# ecg.net
KiCad netlist of a schematic drawn in Altium Designer
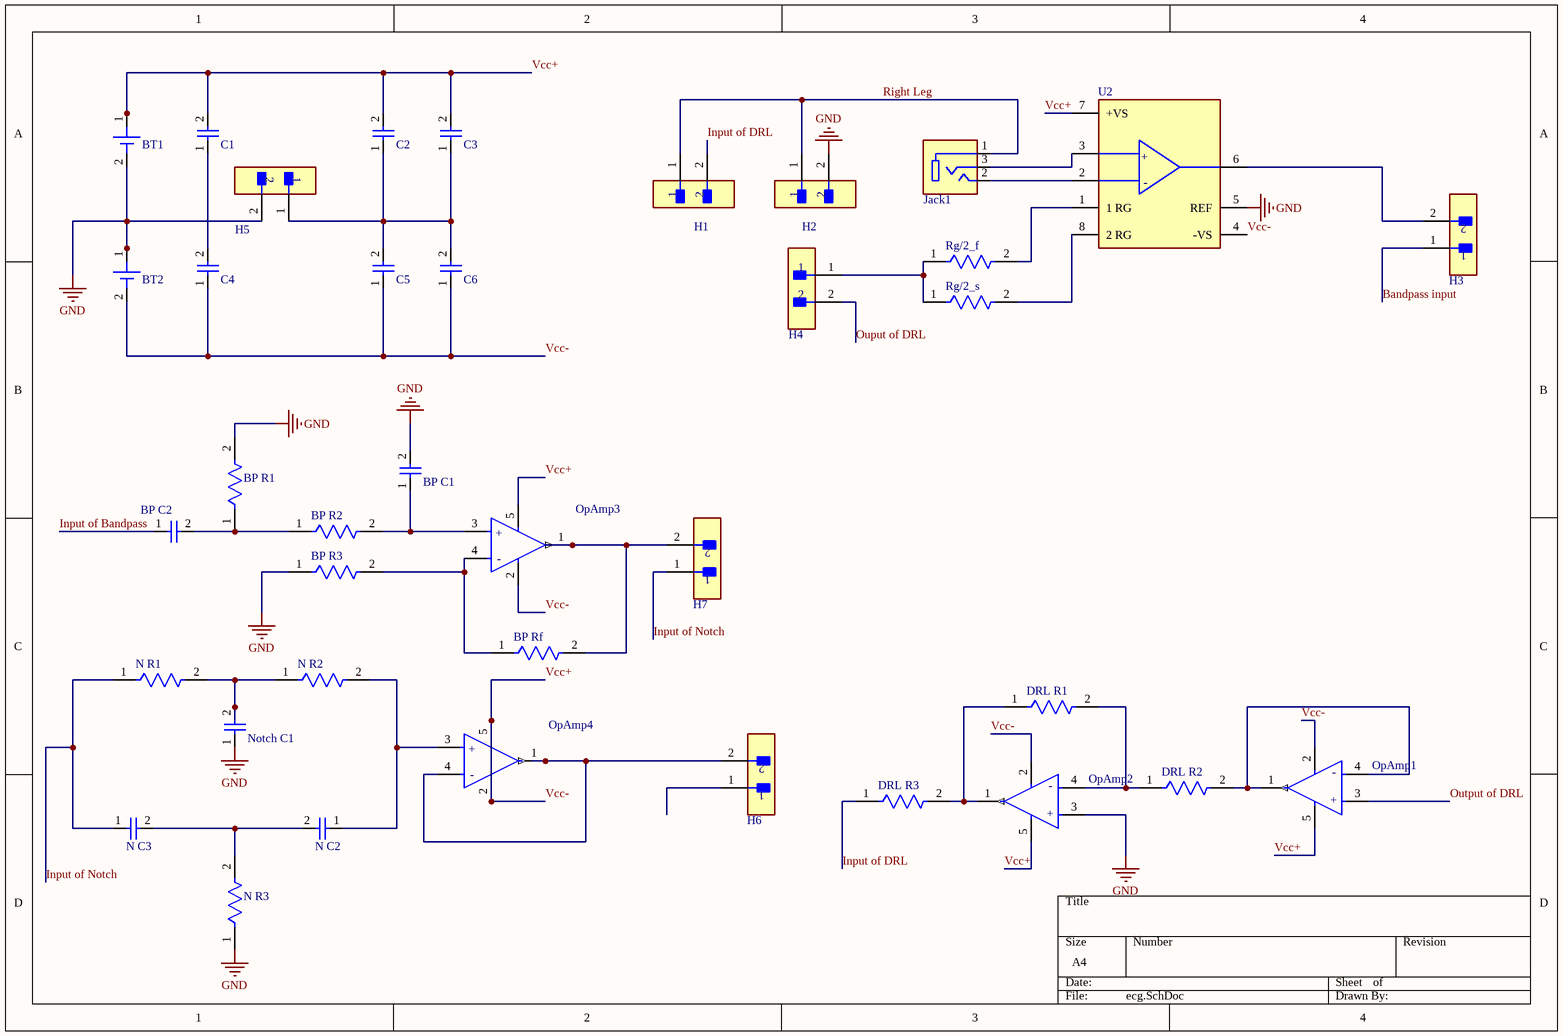
[diagram p0: ecg.SchDoc]

(export (version "E")
  (design (tool "Eeschema 10.0.6"))
  (components
    (comp (ref "BP C1")
      (value "08052U220GAT2A")
      (footprint "CAPC2013X115X51ML20T26")
      (fields (field (name "MANUFACTURER") "AVX Interconnect / Elco"))
      (libsource (lib "Sushil_PCB") (part "CMP-2007-04866-1"))
    )
    (comp (ref "BP C2")
      (value "08052U220GAT2A")
      (footprint "CAPC2013X115X51ML20T26")
      (fields (field (name "MANUFACTURER") "AVX Interconnect / Elco"))
      (libsource (lib "Sushil_PCB") (part "CMP-2007-04866-1"))
    )
    (comp (ref "BP R1")
      (value "CRCW08053K30FKEA")
      (footprint "FP-CRCW0805-e3-MFG")
      (description "RES Thick Film, 3.3kΩ, 1%, 0.125W, 100ppm/°C, 0805")
      (fields (field (name "TOLERANCE") "1%"))
      (libsource (lib "Sushil_PCB") (part "CMP-2001-03876-2"))
    )
    (comp (ref "BP R2")
      (value "CRCW08053K30FKEA")
      (footprint "FP-CRCW0805-e3-MFG")
      (description "RES Thick Film, 3.3kΩ, 1%, 0.125W, 100ppm/°C, 0805")
      (fields (field (name "TOLERANCE") "1%"))
      (libsource (lib "Sushil_PCB") (part "CMP-2001-03876-2"))
    )
    (comp (ref "BP R3")
      (value "CRCW08053K30FKEA")
      (footprint "FP-CRCW0805-e3-MFG")
      (description "RES Thick Film, 3.3kΩ, 1%, 0.125W, 100ppm/°C, 0805")
      (fields (field (name "TOLERANCE") "1%"))
      (libsource (lib "Sushil_PCB") (part "CMP-2001-03876-2"))
    )
    (comp (ref "BP Rf")
      (value "CRCW08053K30FKEA")
      (footprint "FP-CRCW0805-e3-MFG")
      (description "RES Thick Film, 3.3kΩ, 1%, 0.125W, 100ppm/°C, 0805")
      (fields (field (name "TOLERANCE") "1%"))
      (libsource (lib "Sushil_PCB") (part "CMP-2001-03876-2"))
    )
    (comp (ref "BT1")
      (value "BK-913-TR")
      (footprint "BAT_BK-913-TR")
      (description "Battery Retainer Coin, 20.0mm 1 Cell PC Pin")
      (fields (field (name "DIGI-KEY_PART_NUMBER") "BK-913-CT-ND") (field (name "MF") "MPD (Memory"))
      (libsource (lib "Sushil_PCB") (part "BK-913-TR"))
    )
    (comp (ref "BT2")
      (value "BK-913-TR")
      (footprint "BAT_BK-913-TR")
      (description "Battery Retainer Coin, 20.0mm 1 Cell PC Pin")
      (fields (field (name "DIGI-KEY_PART_NUMBER") "BK-913-CT-ND") (field (name "MF") "MPD (Memory"))
      (libsource (lib "Sushil_PCB") (part "BK-913-TR"))
    )
    (comp (ref "C1")
      (value "08052U220GAT2A")
      (footprint "CAPC2013X115X51ML20T26")
      (fields (field (name "MANUFACTURER") "AVX Interconnect / Elco"))
      (libsource (lib "Sushil_PCB") (part "CMP-2007-04866-1"))
    )
    (comp (ref "C2")
      (value "08052U220GAT2A")
      (footprint "CAPC2013X115X51ML20T26")
      (fields (field (name "MANUFACTURER") "AVX Interconnect / Elco"))
      (libsource (lib "Sushil_PCB") (part "CMP-2007-04866-1"))
    )
    (comp (ref "C3")
      (value "08052U220GAT2A")
      (footprint "CAPC2013X115X51ML20T26")
      (fields (field (name "MANUFACTURER") "AVX Interconnect / Elco"))
      (libsource (lib "Sushil_PCB") (part "CMP-2007-04866-1"))
    )
    (comp (ref "C4")
      (value "08052U220GAT2A")
      (footprint "CAPC2013X115X51ML20T26")
      (fields (field (name "MANUFACTURER") "AVX Interconnect / Elco"))
      (libsource (lib "Sushil_PCB") (part "CMP-2007-04866-1"))
    )
    (comp (ref "C5")
      (value "08052U220GAT2A")
      (footprint "CAPC2013X115X51ML20T26")
      (fields (field (name "MANUFACTURER") "AVX Interconnect / Elco"))
      (libsource (lib "Sushil_PCB") (part "CMP-2007-04866-1"))
    )
    (comp (ref "C6")
      (value "08052U220GAT2A")
      (footprint "CAPC2013X115X51ML20T26")
      (fields (field (name "MANUFACTURER") "AVX Interconnect / Elco"))
      (libsource (lib "Sushil_PCB") (part "CMP-2007-04866-1"))
    )
    (comp (ref "DRL R1")
      (value "CRCW08053K30FKEA")
      (footprint "FP-CRCW0805-e3-MFG")
      (description "RES Thick Film, 3.3kΩ, 1%, 0.125W, 100ppm/°C, 0805")
      (fields (field (name "TOLERANCE") "1%"))
      (libsource (lib "Sushil_PCB") (part "CMP-2001-03876-2"))
    )
    (comp (ref "DRL R2")
      (value "CRCW08053K30FKEA")
      (footprint "FP-CRCW0805-e3-MFG")
      (description "RES Thick Film, 3.3kΩ, 1%, 0.125W, 100ppm/°C, 0805")
      (fields (field (name "TOLERANCE") "1%"))
      (libsource (lib "Sushil_PCB") (part "CMP-2001-03876-2"))
    )
    (comp (ref "DRL R3")
      (value "CRCW08053K30FKEA")
      (footprint "FP-CRCW0805-e3-MFG")
      (description "RES Thick Film, 3.3kΩ, 1%, 0.125W, 100ppm/°C, 0805")
      (fields (field (name "TOLERANCE") "1%"))
      (libsource (lib "Sushil_PCB") (part "CMP-2001-03876-2"))
    )
    (comp (ref "H1")
      (value "TSW-102-07-L-S")
      (footprint "FP-TSW-102-07-L-S-MFG")
      (description "CONN HEADER VERT 2POS 2.54MM")
      (libsource (lib "") (part "CMP-02766-001428-1_2"))
    )
    (comp (ref "H2")
      (value "TSW-102-07-L-S")
      (footprint "FP-TSW-102-07-L-S-MFG")
      (description "CONN HEADER VERT 2POS 2.54MM")
      (libsource (lib "") (part "CMP-02766-001428-1_2"))
    )
    (comp (ref "H3")
      (value "TSW-102-07-L-S")
      (footprint "FP-TSW-102-07-L-S-MFG")
      (description "CONN HEADER VERT 2POS 2.54MM")
      (libsource (lib "") (part "CMP-02766-001428-1_1"))
    )
    (comp (ref "H4")
      (value "TSW-102-07-L-S")
      (footprint "FP-TSW-102-07-L-S-MFG")
      (description "CONN HEADER VERT 2POS 2.54MM")
      (libsource (lib "") (part "CMP-02766-001428-1_3"))
    )
    (comp (ref "H5")
      (value "TSW-102-07-L-S")
      (footprint "FP-TSW-102-07-L-S-MFG")
      (description "CONN HEADER VERT 2POS 2.54MM")
      (libsource (lib "Sushil_PCB") (part "CMP-02766-001428-1"))
    )
    (comp (ref "H6")
      (value "TSW-102-07-L-S")
      (footprint "FP-TSW-102-07-L-S-MFG")
      (description "CONN HEADER VERT 2POS 2.54MM")
      (libsource (lib "") (part "CMP-02766-001428-1_1"))
    )
    (comp (ref "H7")
      (value "TSW-102-07-L-S")
      (footprint "FP-TSW-102-07-L-S-MFG")
      (description "CONN HEADER VERT 2POS 2.54MM")
      (libsource (lib "") (part "CMP-02766-001428-1_1"))
    )
    (comp (ref "Jack1")
      (value "SJ-3523-SMT-TR")
      (footprint "CUI_SJ-3523-SMT-TR")
      (description "<b>Audio Jack Connector</b> 3.5 mm Low Profile Surface Mount Stereo Jack, 3 Pin Right-Angle")
      (libsource (lib "Sushil_PCB") (part "SJ-3523-SMT-TR"))
    )
    (comp (ref "N C2")
      (value "08052U220GAT2A")
      (footprint "CAPC2013X115X51ML20T26")
      (fields (field (name "MANUFACTURER") "AVX Interconnect / Elco"))
      (libsource (lib "Sushil_PCB") (part "CMP-2007-04866-1"))
    )
    (comp (ref "N C3")
      (value "08052U220GAT2A")
      (footprint "CAPC2013X115X51ML20T26")
      (fields (field (name "MANUFACTURER") "AVX Interconnect / Elco"))
      (libsource (lib "Sushil_PCB") (part "CMP-2007-04866-1"))
    )
    (comp (ref "N R1")
      (value "CRCW08053K30FKEA")
      (footprint "FP-CRCW0805-e3-MFG")
      (description "RES Thick Film, 3.3kΩ, 1%, 0.125W, 100ppm/°C, 0805")
      (fields (field (name "TOLERANCE") "1%"))
      (libsource (lib "Sushil_PCB") (part "CMP-2001-03876-2"))
    )
    (comp (ref "N R2")
      (value "CRCW08053K30FKEA")
      (footprint "FP-CRCW0805-e3-MFG")
      (description "RES Thick Film, 3.3kΩ, 1%, 0.125W, 100ppm/°C, 0805")
      (fields (field (name "TOLERANCE") "1%"))
      (libsource (lib "Sushil_PCB") (part "CMP-2001-03876-2"))
    )
    (comp (ref "N R3")
      (value "CRCW08053K30FKEA")
      (footprint "FP-CRCW0805-e3-MFG")
      (description "RES Thick Film, 3.3kΩ, 1%, 0.125W, 100ppm/°C, 0805")
      (fields (field (name "TOLERANCE") "1%"))
      (libsource (lib "Sushil_PCB") (part "CMP-2001-03876-2"))
    )
    (comp (ref "Notch C1")
      (value "08052U220GAT2A")
      (footprint "CAPC2013X115X51ML20T26")
      (fields (field (name "MANUFACTURER") "AVX Interconnect / Elco"))
      (libsource (lib "Sushil_PCB") (part "CMP-2007-04866-1"))
    )
    (comp (ref "OpAmp1")
      (value "TLV521DCKT")
      (footprint "FP-DCK0005A-IPC_C")
      (description "IC CMOS 1 CIRCUIT SC70-5")
      (libsource (lib "Sushil_PCB") (part "CMP-04895-000072-1"))
    )
    (comp (ref "OpAmp2")
      (value "TLV521DCKT")
      (footprint "FP-DCK0005A-IPC_C")
      (description "IC CMOS 1 CIRCUIT SC70-5")
      (libsource (lib "Sushil_PCB") (part "CMP-04895-000072-1"))
    )
    (comp (ref "OpAmp3")
      (value "TLV521DCKT")
      (footprint "FP-DCK0005A-IPC_C")
      (description "IC CMOS 1 CIRCUIT SC70-5")
      (libsource (lib "Sushil_PCB") (part "CMP-04895-000072-1"))
    )
    (comp (ref "OpAmp4")
      (value "TLV521DCKT")
      (footprint "FP-DCK0005A-IPC_C")
      (description "IC CMOS 1 CIRCUIT SC70-5")
      (libsource (lib "Sushil_PCB") (part "CMP-04895-000072-1"))
    )
    (comp (ref "Rg/2_f")
      (value "CRCW08053K30FKEA")
      (footprint "FP-CRCW0805-e3-MFG")
      (description "RES Thick Film, 3.3kΩ, 1%, 0.125W, 100ppm/°C, 0805")
      (fields (field (name "TOLERANCE") "1%"))
      (libsource (lib "Sushil_PCB") (part "CMP-2001-03876-2"))
    )
    (comp (ref "Rg/2_s")
      (value "CRCW08053K30FKEA")
      (footprint "FP-CRCW0805-e3-MFG")
      (description "RES Thick Film, 3.3kΩ, 1%, 0.125W, 100ppm/°C, 0805")
      (fields (field (name "TOLERANCE") "1%"))
      (libsource (lib "Sushil_PCB") (part "CMP-2001-03876-2"))
    )
    (comp (ref "U2")
      (value "AD620ARZ-REEL7")
      (footprint "FP-R-8-IPC_A")
      (description "IC INST AMP 1 CIRCUIT 8SOIC")
      (libsource (lib "Sushil_PCB") (part "CMP-09116-000354-1"))
    )
  )
  (nets
    (net (code "1") (name "/Bandpass input") (class "Default")
      (node (ref "H3") (pin "1") (pinfunction "1_1") (pintype "passive"))
    )
    (net (code "2") (name "/Input of Bandpass") (class "Default")
      (node (ref "BP C2") (pin "1") (pinfunction "1_1") (pintype "passive"))
    )
    (net (code "3") (name "/Input of DRL") (class "Default")
      (node (ref "DRL R3") (pin "1") (pinfunction "1_1") (pintype "passive"))
      (node (ref "H1") (pin "2") (pinfunction "2_2") (pintype "passive"))
    )
    (net (code "4") (name "/Input of Notch") (class "Default")
      (node (ref "H7") (pin "1") (pinfunction "1_1") (pintype "passive"))
      (node (ref "N C3") (pin "1") (pinfunction "1_1") (pintype "passive"))
      (node (ref "N R1") (pin "1") (pinfunction "1_1") (pintype "passive"))
    )
    (net (code "5") (name "/Ouput of DRL") (class "Default")
      (node (ref "H4") (pin "2") (pinfunction "2_2") (pintype "passive"))
    )
    (net (code "6") (name "/Output of DRL") (class "Default")
      (node (ref "OpAmp1") (pin "3") (pinfunction "IN+_3") (pintype "tri_state"))
    )
    (net (code "7") (name "/Right Leg") (class "Default")
      (node (ref "H1") (pin "1") (pinfunction "1_1") (pintype "passive"))
      (node (ref "H2") (pin "1") (pinfunction "1_1") (pintype "passive"))
      (node (ref "Jack1") (pin "1") (pinfunction "1_1") (pintype "passive"))
    )
    (net (code "8") (name "/Vcc+") (class "Default")
      (node (ref "BT1") (pin "1") (pinfunction "POS_1") (pintype "passive"))
      (node (ref "BT2") (pin "2") (pinfunction "NEG_2") (pintype "passive"))
      (node (ref "C1") (pin "2") (pinfunction "2_2") (pintype "passive"))
      (node (ref "C2") (pin "2") (pinfunction "2_2") (pintype "passive"))
      (node (ref "C3") (pin "2") (pinfunction "2_2") (pintype "passive"))
      (node (ref "C4") (pin "1") (pinfunction "1_1") (pintype "passive"))
      (node (ref "C5") (pin "1") (pinfunction "1_1") (pintype "passive"))
      (node (ref "C6") (pin "1") (pinfunction "1_1") (pintype "passive"))
      (node (ref "OpAmp1") (pin "2") (pinfunction "V-_2") (pintype "power_in"))
      (node (ref "OpAmp1") (pin "5") (pinfunction "V+_5") (pintype "power_in"))
      (node (ref "OpAmp2") (pin "2") (pinfunction "V-_2") (pintype "power_in"))
      (node (ref "OpAmp2") (pin "5") (pinfunction "V+_5") (pintype "power_in"))
      (node (ref "OpAmp3") (pin "2") (pinfunction "V-_2") (pintype "power_in"))
      (node (ref "OpAmp3") (pin "5") (pinfunction "V+_5") (pintype "power_in"))
      (node (ref "OpAmp4") (pin "2") (pinfunction "V-_2") (pintype "power_in"))
      (node (ref "OpAmp4") (pin "5") (pinfunction "V+_5") (pintype "power_in"))
      (node (ref "U2") (pin "4") (pinfunction "-VS_4") (pintype "power_in"))
      (node (ref "U2") (pin "7") (pinfunction "+VS_7") (pintype "power_in"))
    )
    (net (code "9") (name "GND") (class "Default")
      (node (ref "BP C1") (pin "2") (pinfunction "2_2") (pintype "passive"))
      (node (ref "BP R1") (pin "2") (pinfunction "2_2") (pintype "passive"))
      (node (ref "BP R3") (pin "1") (pinfunction "1_1") (pintype "passive"))
      (node (ref "BT1") (pin "2") (pinfunction "NEG_2") (pintype "passive"))
      (node (ref "BT2") (pin "1") (pinfunction "POS_1") (pintype "passive"))
      (node (ref "H2") (pin "2") (pinfunction "2_2") (pintype "passive"))
      (node (ref "H5") (pin "2") (pinfunction "2_2") (pintype "passive"))
      (node (ref "N R3") (pin "1") (pinfunction "1_1") (pintype "passive"))
      (node (ref "Notch C1") (pin "1") (pinfunction "1_1") (pintype "passive"))
      (node (ref "OpAmp2") (pin "3") (pinfunction "IN+_3") (pintype "tri_state"))
      (node (ref "U2") (pin "5") (pinfunction "REF_5") (pintype "passive"))
    )
    (net (code "10") (name "Net-(BP C2-Pad2)") (class "Default")
      (node (ref "BP C2") (pin "2") (pinfunction "2_2") (pintype "passive"))
      (node (ref "BP R1") (pin "1") (pinfunction "1_1") (pintype "passive"))
      (node (ref "BP R2") (pin "1") (pinfunction "1_1") (pintype "passive"))
    )
    (net (code "11") (name "Net-(C1-Pad1)") (class "Default")
      (node (ref "C1") (pin "1") (pinfunction "1_1") (pintype "passive"))
      (node (ref "C4") (pin "2") (pinfunction "2_2") (pintype "passive"))
    )
    (net (code "12") (name "Net-(C2-Pad1)") (class "Default")
      (node (ref "C2") (pin "1") (pinfunction "1_1") (pintype "passive"))
      (node (ref "C3") (pin "1") (pinfunction "1_1") (pintype "passive"))
      (node (ref "C5") (pin "2") (pinfunction "2_2") (pintype "passive"))
      (node (ref "C6") (pin "2") (pinfunction "2_2") (pintype "passive"))
      (node (ref "H5") (pin "1") (pinfunction "1_1") (pintype "passive"))
    )
    (net (code "13") (name "Net-(H4-Pad1)") (class "Default")
      (node (ref "H4") (pin "1") (pinfunction "1_1") (pintype "passive"))
      (node (ref "Rg/2_f") (pin "1") (pinfunction "1_1") (pintype "passive"))
      (node (ref "Rg/2_s") (pin "1") (pinfunction "1_1") (pintype "passive"))
    )
    (net (code "14") (name "Net-(N C2-Pad2)") (class "Default")
      (node (ref "N C2") (pin "2") (pinfunction "2_2") (pintype "passive"))
      (node (ref "N C3") (pin "2") (pinfunction "2_2") (pintype "passive"))
      (node (ref "N R3") (pin "2") (pinfunction "2_2") (pintype "passive"))
    )
    (net (code "15") (name "Net-(N R1-Pad2)") (class "Default")
      (node (ref "N R1") (pin "2") (pinfunction "2_2") (pintype "passive"))
      (node (ref "N R2") (pin "1") (pinfunction "1_1") (pintype "passive"))
      (node (ref "Notch C1") (pin "2") (pinfunction "2_2") (pintype "passive"))
    )
    (net (code "16") (name "Net-(OpAmp1-IN-)") (class "Default")
      (node (ref "DRL R2") (pin "2") (pinfunction "2_2") (pintype "passive"))
      (node (ref "OpAmp1") (pin "1") (pinfunction "OUT_1") (pintype "output"))
      (node (ref "OpAmp1") (pin "4") (pinfunction "IN-_4") (pintype "tri_state"))
    )
    (net (code "17") (name "Net-(OpAmp2-IN-)") (class "Default")
      (node (ref "DRL R1") (pin "2") (pinfunction "2_2") (pintype "passive"))
      (node (ref "DRL R2") (pin "1") (pinfunction "1_1") (pintype "passive"))
      (node (ref "OpAmp2") (pin "4") (pinfunction "IN-_4") (pintype "tri_state"))
    )
    (net (code "18") (name "Net-(OpAmp2-OUT)") (class "Default")
      (node (ref "DRL R1") (pin "1") (pinfunction "1_1") (pintype "passive"))
      (node (ref "DRL R3") (pin "2") (pinfunction "2_2") (pintype "passive"))
      (node (ref "OpAmp2") (pin "1") (pinfunction "OUT_1") (pintype "output"))
    )
    (net (code "19") (name "Net-(OpAmp3-IN+)") (class "Default")
      (node (ref "BP C1") (pin "1") (pinfunction "1_1") (pintype "passive"))
      (node (ref "BP R2") (pin "2") (pinfunction "2_2") (pintype "passive"))
      (node (ref "OpAmp3") (pin "3") (pinfunction "IN+_3") (pintype "tri_state"))
    )
    (net (code "20") (name "Net-(OpAmp3-IN-)") (class "Default")
      (node (ref "BP R3") (pin "2") (pinfunction "2_2") (pintype "passive"))
      (node (ref "BP Rf") (pin "1") (pinfunction "1_1") (pintype "passive"))
      (node (ref "OpAmp3") (pin "4") (pinfunction "IN-_4") (pintype "tri_state"))
    )
    (net (code "21") (name "Net-(OpAmp3-OUT)") (class "Default")
      (node (ref "BP Rf") (pin "2") (pinfunction "2_2") (pintype "passive"))
      (node (ref "H7") (pin "2") (pinfunction "2_2") (pintype "passive"))
      (node (ref "OpAmp3") (pin "1") (pinfunction "OUT_1") (pintype "output"))
    )
    (net (code "22") (name "Net-(OpAmp4-IN+)") (class "Default")
      (node (ref "N C2") (pin "1") (pinfunction "1_1") (pintype "passive"))
      (node (ref "N R2") (pin "2") (pinfunction "2_2") (pintype "passive"))
      (node (ref "OpAmp4") (pin "3") (pinfunction "IN+_3") (pintype "tri_state"))
    )
    (net (code "23") (name "Net-(OpAmp4-IN-)") (class "Default")
      (node (ref "H6") (pin "2") (pinfunction "2_2") (pintype "passive"))
      (node (ref "OpAmp4") (pin "1") (pinfunction "OUT_1") (pintype "output"))
      (node (ref "OpAmp4") (pin "4") (pinfunction "IN-_4") (pintype "tri_state"))
    )
    (net (code "24") (name "Net-(U2-+IN)") (class "Default")
      (node (ref "Jack1") (pin "3") (pinfunction "3_3") (pintype "passive"))
      (node (ref "U2") (pin "3") (pinfunction "+IN_3") (pintype "tri_state"))
    )
    (net (code "25") (name "Net-(U2--IN)") (class "Default")
      (node (ref "Jack1") (pin "2") (pinfunction "2_2") (pintype "passive"))
      (node (ref "U2") (pin "2") (pinfunction "-IN_2") (pintype "tri_state"))
    )
    (net (code "26") (name "Net-(U2-1_RG)") (class "Default")
      (node (ref "Rg/2_f") (pin "2") (pinfunction "2_2") (pintype "passive"))
      (node (ref "U2") (pin "1") (pinfunction "1_RG_1") (pintype "passive"))
    )
    (net (code "27") (name "Net-(U2-2_RG)") (class "Default")
      (node (ref "Rg/2_s") (pin "2") (pinfunction "2_2") (pintype "passive"))
      (node (ref "U2") (pin "8") (pinfunction "2_RG_8") (pintype "passive"))
    )
    (net (code "28") (name "Net-(U2-OUTPUT)") (class "Default")
      (node (ref "H3") (pin "2") (pinfunction "2_2") (pintype "passive"))
      (node (ref "U2") (pin "6") (pinfunction "OUTPUT_6") (pintype "passive"))
    )
    (net (code "29") (name "unconnected-(H6-Pad1)") (class "Default")
      (node (ref "H6") (pin "1") (pinfunction "1_1") (pintype "passive"))
    )
  )
)
